# Arduino_like.net
KiCad netlist of a schematic drawn in EAGLE
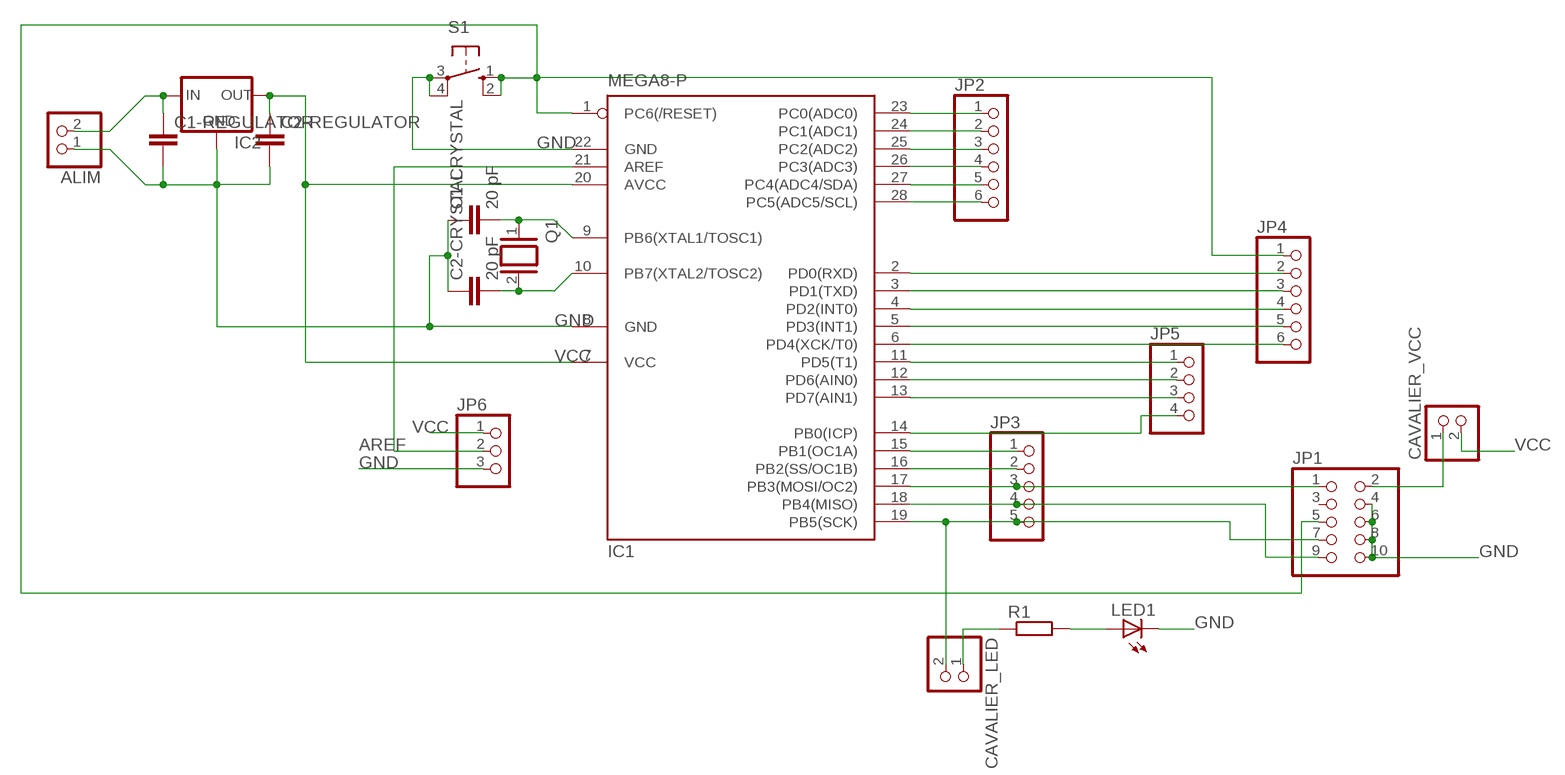
[diagram p0: schematic, sheet 1]

(export (version "E")
  (design (tool "Eeschema 10.0.6"))
  (components
    (comp (ref "ALIM")
      (value "PINHD-1X2")
      (footprint "eagle-import:1X02")
      (libsource (lib "eagle-import") (part "PINHD-1X2"))
    )
    (comp (ref "C1-CRYSTAL")
      (value "20 pF")
      (footprint "eagle-import:C5B5")
      (libsource (lib "eagle-import") (part "C5/5"))
    )
    (comp (ref "C1-REGULATOR")
      (value "C5/3.5")
      (footprint "eagle-import:C5B3.5")
      (libsource (lib "eagle-import") (part "C5/3.5"))
    )
    (comp (ref "C2-CRYSTAL")
      (value "20 pF")
      (footprint "eagle-import:C5B5")
      (libsource (lib "eagle-import") (part "C5/5"))
    )
    (comp (ref "C2-REGULATOR")
      (value "C5/3.5")
      (footprint "eagle-import:C5B3.5")
      (libsource (lib "eagle-import") (part "C5/3.5"))
    )
    (comp (ref "CAVALIER_LED")
      (value "PINHD-1X2")
      (footprint "eagle-import:1X02")
      (libsource (lib "eagle-import") (part "PINHD-1X2"))
    )
    (comp (ref "CAVALIER_VCC")
      (value "PINHD-1X2")
      (footprint "eagle-import:1X02")
      (libsource (lib "eagle-import") (part "PINHD-1X2"))
    )
    (comp (ref "IC1")
      (value "MEGA8-P")
      (footprint "eagle-import:DIL28-3")
      (libsource (lib "eagle-import") (part "MEGA8-P"))
    )
    (comp (ref "IC2")
      (value "78XXS")
      (footprint "eagle-import:78XXS")
      (libsource (lib "eagle-import") (part "78XXS"))
    )
    (comp (ref "JP1")
      (value "PINHD-2X5")
      (footprint "eagle-import:2X05")
      (libsource (lib "eagle-import") (part "PINHD-2X5"))
    )
    (comp (ref "JP2")
      (value "PINHD-1X6")
      (footprint "eagle-import:1X06")
      (libsource (lib "eagle-import") (part "PINHD-1X6"))
    )
    (comp (ref "JP3")
      (value "PINHD-1X5")
      (footprint "eagle-import:1X05")
      (libsource (lib "eagle-import") (part "PINHD-1X5"))
    )
    (comp (ref "JP4")
      (value "PINHD-1X6")
      (footprint "eagle-import:1X06")
      (libsource (lib "eagle-import") (part "PINHD-1X6"))
    )
    (comp (ref "JP5")
      (value "PINHD-1X4")
      (footprint "eagle-import:1X04")
      (libsource (lib "eagle-import") (part "PINHD-1X4"))
    )
    (comp (ref "JP6")
      (value "PINHD-1X3")
      (footprint "eagle-import:1X03")
      (libsource (lib "eagle-import") (part "PINHD-1X3"))
    )
    (comp (ref "LED1")
      (value "LED3MM")
      (footprint "eagle-import:LED3MM")
      (libsource (lib "eagle-import") (part "LED3MM"))
    )
    (comp (ref "Q1")
      (value "XTAL/S")
      (footprint "eagle-import:QS")
      (libsource (lib "eagle-import") (part "XTAL/S"))
    )
    (comp (ref "R1")
      (value "R-EU_0204/7")
      (footprint "eagle-import:0204_7")
      (libsource (lib "eagle-import") (part "R-EU_0204/7"))
    )
    (comp (ref "S1")
      (value "10-XX")
      (footprint "eagle-import:B3F-10XX")
      (fields (field (name "MPN") "B3F-1000"))
      (libsource (lib "eagle-import") (part "10-XX"))
    )
  )
  (nets
    (net (code "1") (name "/AREF") (class "Default")
      (node (ref "IC1") (pin "21") (pinfunction "AREF_21") (pintype "passive"))
      (node (ref "JP6") (pin "2") (pinfunction "2_2") (pintype "passive"))
    )
    (net (code "2") (name "/GND") (class "Default")
      (node (ref "ALIM") (pin "1") (pinfunction "1_1") (pintype "passive"))
      (node (ref "C1-CRYSTAL") (pin "1") (pinfunction "1_1") (pintype "passive"))
      (node (ref "C1-REGULATOR") (pin "2") (pinfunction "2_2") (pintype "passive"))
      (node (ref "C2-CRYSTAL") (pin "1") (pinfunction "1_1") (pintype "passive"))
      (node (ref "C2-REGULATOR") (pin "2") (pinfunction "2_2") (pintype "passive"))
      (node (ref "IC1") (pin "22") (pinfunction "GND_22") (pintype "power_in"))
      (node (ref "IC1") (pin "8") (pinfunction "GND_8") (pintype "power_in"))
      (node (ref "IC2") (pin "GND") (pinfunction "GND_GND") (pintype "input"))
      (node (ref "JP1") (pin "10") (pinfunction "10_10") (pintype "passive"))
      (node (ref "JP1") (pin "4") (pinfunction "4_4") (pintype "passive"))
      (node (ref "JP1") (pin "6") (pinfunction "6_6") (pintype "passive"))
      (node (ref "JP1") (pin "8") (pinfunction "8_8") (pintype "passive"))
      (node (ref "JP6") (pin "3") (pinfunction "3_3") (pintype "passive"))
      (node (ref "LED1") (pin "K") (pinfunction "C_K") (pintype "passive"))
      (node (ref "S1") (pin "3") (pinfunction "P_3") (pintype "passive"))
      (node (ref "S1") (pin "4") (pinfunction "P1_4") (pintype "passive"))
    )
    (net (code "3") (name "/VCC") (class "Default")
      (node (ref "C2-REGULATOR") (pin "1") (pinfunction "1_1") (pintype "passive"))
      (node (ref "CAVALIER_VCC") (pin "2") (pinfunction "2_2") (pintype "passive"))
      (node (ref "IC1") (pin "20") (pinfunction "AVCC_20") (pintype "power_in"))
      (node (ref "IC1") (pin "7") (pinfunction "VCC_7") (pintype "power_in"))
      (node (ref "IC2") (pin "OUT") (pinfunction "OUT_OUT") (pintype "passive"))
      (node (ref "JP6") (pin "1") (pinfunction "1_1") (pintype "passive"))
    )
    (net (code "4") (name "Net-(ALIM-Pad2)") (class "Default")
      (node (ref "ALIM") (pin "2") (pinfunction "2_2") (pintype "passive"))
      (node (ref "C1-REGULATOR") (pin "1") (pinfunction "1_1") (pintype "passive"))
      (node (ref "IC2") (pin "IN") (pinfunction "IN_IN") (pintype "input"))
    )
    (net (code "5") (name "Net-(CAVALIER_LED-Pad1)") (class "Default")
      (node (ref "CAVALIER_LED") (pin "1") (pinfunction "1_1") (pintype "passive"))
      (node (ref "R1") (pin "1") (pinfunction "1_1") (pintype "passive"))
    )
    (net (code "6") (name "Net-(CAVALIER_VCC-Pad1)") (class "Default")
      (node (ref "CAVALIER_VCC") (pin "1") (pinfunction "1_1") (pintype "passive"))
      (node (ref "JP1") (pin "2") (pinfunction "2_2") (pintype "passive"))
    )
    (net (code "7") (name "Net-(IC1-PB0(ICP))") (class "Default")
      (node (ref "IC1") (pin "14") (pinfunction "PB0(ICP)_14") (pintype "bidirectional"))
      (node (ref "JP5") (pin "4") (pinfunction "4_4") (pintype "passive"))
    )
    (net (code "8") (name "Net-(IC1-PB1(OC1A))") (class "Default")
      (node (ref "IC1") (pin "15") (pinfunction "PB1(OC1A)_15") (pintype "bidirectional"))
      (node (ref "JP3") (pin "1") (pinfunction "1_1") (pintype "passive"))
    )
    (net (code "9") (name "Net-(IC1-PB2(SS{slash}OC1B))") (class "Default")
      (node (ref "IC1") (pin "16") (pinfunction "PB2(SS/OC1B)_16") (pintype "bidirectional"))
      (node (ref "JP3") (pin "2") (pinfunction "2_2") (pintype "passive"))
    )
    (net (code "10") (name "Net-(IC1-PB3(MOSI{slash}OC2))") (class "Default")
      (node (ref "IC1") (pin "17") (pinfunction "PB3(MOSI/OC2)_17") (pintype "bidirectional"))
      (node (ref "JP1") (pin "1") (pinfunction "1_1") (pintype "passive"))
      (node (ref "JP3") (pin "3") (pinfunction "3_3") (pintype "passive"))
    )
    (net (code "11") (name "Net-(IC1-PB4(MISO))") (class "Default")
      (node (ref "IC1") (pin "18") (pinfunction "PB4(MISO)_18") (pintype "bidirectional"))
      (node (ref "JP1") (pin "9") (pinfunction "9_9") (pintype "passive"))
      (node (ref "JP3") (pin "4") (pinfunction "4_4") (pintype "passive"))
    )
    (net (code "12") (name "Net-(IC1-PB5(SCK))") (class "Default")
      (node (ref "CAVALIER_LED") (pin "2") (pinfunction "2_2") (pintype "passive"))
      (node (ref "IC1") (pin "19") (pinfunction "PB5(SCK)_19") (pintype "bidirectional"))
      (node (ref "JP1") (pin "7") (pinfunction "7_7") (pintype "passive"))
      (node (ref "JP3") (pin "5") (pinfunction "5_5") (pintype "passive"))
    )
    (net (code "13") (name "Net-(IC1-PB6(XTAL1{slash}TOSC1))") (class "Default")
      (node (ref "C1-CRYSTAL") (pin "2") (pinfunction "2_2") (pintype "passive"))
      (node (ref "IC1") (pin "9") (pinfunction "PB6(XTAL1/TOSC1)_9") (pintype "bidirectional"))
      (node (ref "Q1") (pin "1") (pinfunction "1_1") (pintype "passive"))
    )
    (net (code "14") (name "Net-(IC1-PB7(XTAL2{slash}TOSC2))") (class "Default")
      (node (ref "C2-CRYSTAL") (pin "2") (pinfunction "2_2") (pintype "passive"))
      (node (ref "IC1") (pin "10") (pinfunction "PB7(XTAL2/TOSC2)_10") (pintype "bidirectional"))
      (node (ref "Q1") (pin "2") (pinfunction "2_2") (pintype "passive"))
    )
    (net (code "15") (name "Net-(IC1-PC0(ADC0))") (class "Default")
      (node (ref "IC1") (pin "23") (pinfunction "PC0(ADC0)_23") (pintype "bidirectional"))
      (node (ref "JP2") (pin "1") (pinfunction "1_1") (pintype "passive"))
    )
    (net (code "16") (name "Net-(IC1-PC1(ADC1))") (class "Default")
      (node (ref "IC1") (pin "24") (pinfunction "PC1(ADC1)_24") (pintype "bidirectional"))
      (node (ref "JP2") (pin "2") (pinfunction "2_2") (pintype "passive"))
    )
    (net (code "17") (name "Net-(IC1-PC2(ADC2))") (class "Default")
      (node (ref "IC1") (pin "25") (pinfunction "PC2(ADC2)_25") (pintype "bidirectional"))
      (node (ref "JP2") (pin "3") (pinfunction "3_3") (pintype "passive"))
    )
    (net (code "18") (name "Net-(IC1-PC3(ADC3))") (class "Default")
      (node (ref "IC1") (pin "26") (pinfunction "PC3(ADC3)_26") (pintype "bidirectional"))
      (node (ref "JP2") (pin "4") (pinfunction "4_4") (pintype "passive"))
    )
    (net (code "19") (name "Net-(IC1-PC4(ADC4{slash}SDA))") (class "Default")
      (node (ref "IC1") (pin "27") (pinfunction "PC4(ADC4/SDA)_27") (pintype "bidirectional"))
      (node (ref "JP2") (pin "5") (pinfunction "5_5") (pintype "passive"))
    )
    (net (code "20") (name "Net-(IC1-PC5(ADC5{slash}SCL))") (class "Default")
      (node (ref "IC1") (pin "28") (pinfunction "PC5(ADC5/SCL)_28") (pintype "bidirectional"))
      (node (ref "JP2") (pin "6") (pinfunction "6_6") (pintype "passive"))
    )
    (net (code "21") (name "Net-(IC1-PC6({slash}RESET))") (class "Default")
      (node (ref "IC1") (pin "1") (pinfunction "PC6(/RESET)_1") (pintype "bidirectional"))
      (node (ref "JP1") (pin "5") (pinfunction "5_5") (pintype "passive"))
      (node (ref "JP4") (pin "1") (pinfunction "1_1") (pintype "passive"))
      (node (ref "S1") (pin "1") (pinfunction "S_1") (pintype "passive"))
      (node (ref "S1") (pin "2") (pinfunction "S1_2") (pintype "passive"))
    )
    (net (code "22") (name "Net-(IC1-PD0(RXD))") (class "Default")
      (node (ref "IC1") (pin "2") (pinfunction "PD0(RXD)_2") (pintype "bidirectional"))
      (node (ref "JP4") (pin "2") (pinfunction "2_2") (pintype "passive"))
    )
    (net (code "23") (name "Net-(IC1-PD1(TXD))") (class "Default")
      (node (ref "IC1") (pin "3") (pinfunction "PD1(TXD)_3") (pintype "bidirectional"))
      (node (ref "JP4") (pin "3") (pinfunction "3_3") (pintype "passive"))
    )
    (net (code "24") (name "Net-(IC1-PD2(INT0))") (class "Default")
      (node (ref "IC1") (pin "4") (pinfunction "PD2(INT0)_4") (pintype "bidirectional"))
      (node (ref "JP4") (pin "4") (pinfunction "4_4") (pintype "passive"))
    )
    (net (code "25") (name "Net-(IC1-PD3(INT1))") (class "Default")
      (node (ref "IC1") (pin "5") (pinfunction "PD3(INT1)_5") (pintype "bidirectional"))
      (node (ref "JP4") (pin "5") (pinfunction "5_5") (pintype "passive"))
    )
    (net (code "26") (name "Net-(IC1-PD4(XCK{slash}T0))") (class "Default")
      (node (ref "IC1") (pin "6") (pinfunction "PD4(XCK/T0)_6") (pintype "bidirectional"))
      (node (ref "JP4") (pin "6") (pinfunction "6_6") (pintype "passive"))
    )
    (net (code "27") (name "Net-(IC1-PD5(T1))") (class "Default")
      (node (ref "IC1") (pin "11") (pinfunction "PD5(T1)_11") (pintype "bidirectional"))
      (node (ref "JP5") (pin "1") (pinfunction "1_1") (pintype "passive"))
    )
    (net (code "28") (name "Net-(IC1-PD6(AIN0))") (class "Default")
      (node (ref "IC1") (pin "12") (pinfunction "PD6(AIN0)_12") (pintype "bidirectional"))
      (node (ref "JP5") (pin "2") (pinfunction "2_2") (pintype "passive"))
    )
    (net (code "29") (name "Net-(IC1-PD7(AIN1))") (class "Default")
      (node (ref "IC1") (pin "13") (pinfunction "PD7(AIN1)_13") (pintype "bidirectional"))
      (node (ref "JP5") (pin "3") (pinfunction "3_3") (pintype "passive"))
    )
    (net (code "30") (name "Net-(LED1-PadA)") (class "Default")
      (node (ref "LED1") (pin "A") (pinfunction "A_A") (pintype "passive"))
      (node (ref "R1") (pin "2") (pinfunction "2_2") (pintype "passive"))
    )
    (net (code "31") (name "unconnected-(JP1-Pad3)") (class "Default")
      (node (ref "JP1") (pin "3") (pinfunction "3_3") (pintype "passive"))
    )
  )
)
